# sch.net
KiCad netlist of a schematic drawn in Altium Designer
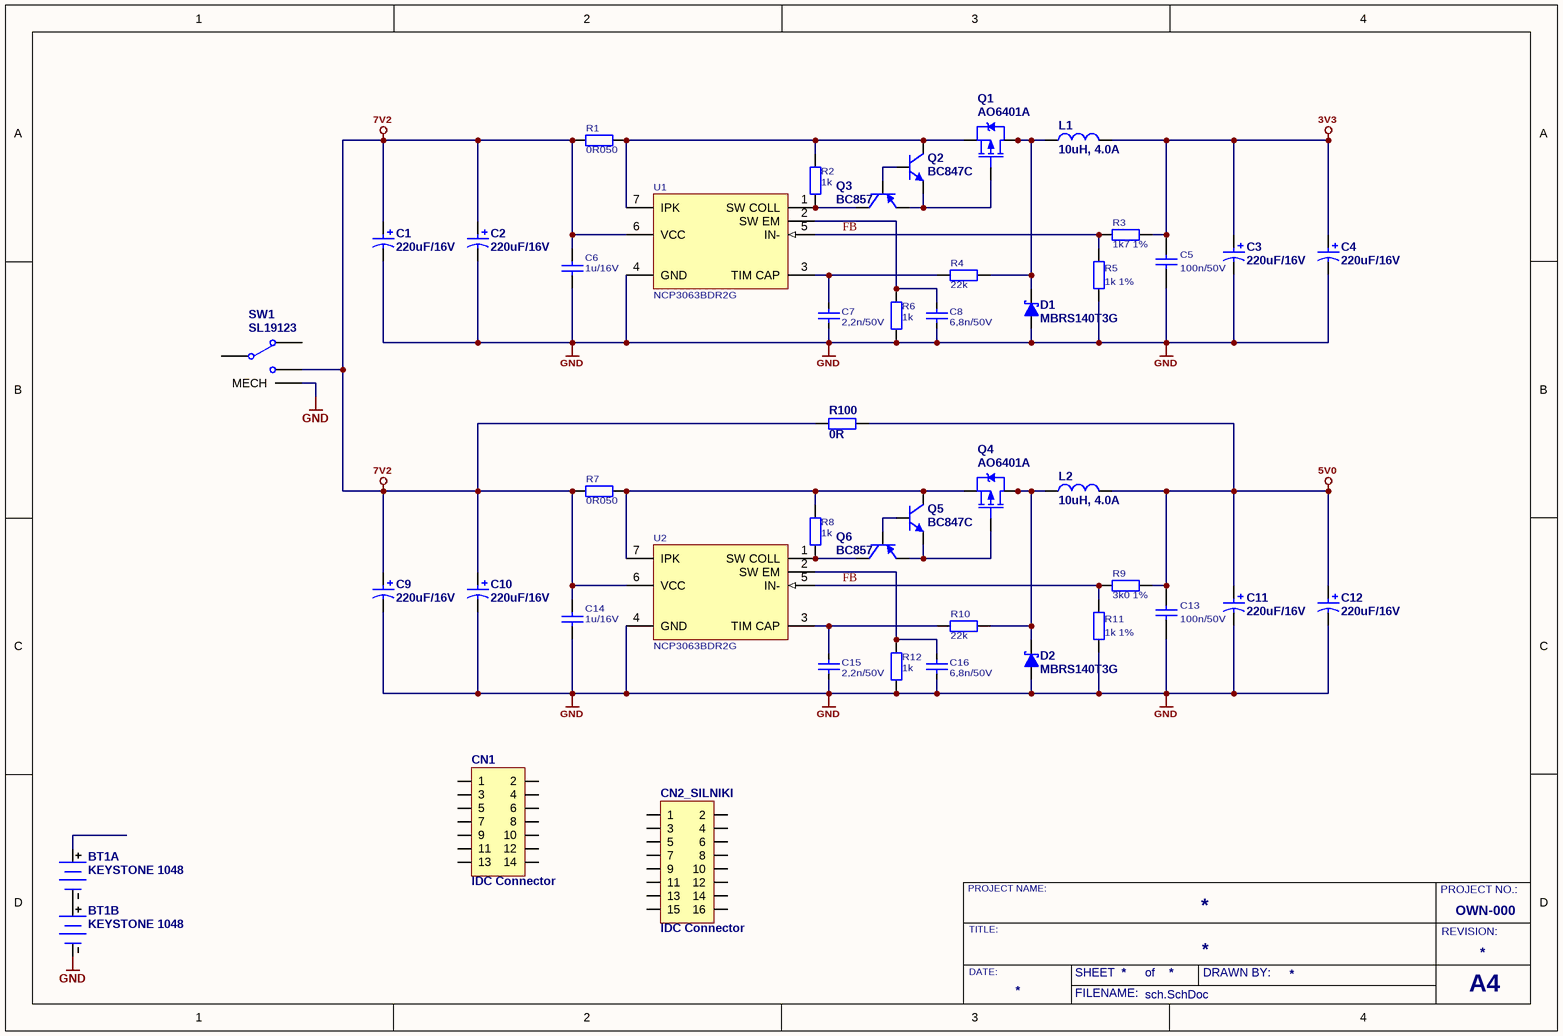
[diagram p0: sch.SchDoc]

(export (version "E")
  (design (tool "Eeschema 10.0.6"))
  (components
    (comp (ref "BT1")
      (value "KEYSTONE 1048")
      (footprint "KEYSTONE_1048")
      (description "2x 18650 LiPo Acu in the KEYSTONE 1048 Holder")
      (libsource (lib "baterries_and_accus") (part "18650_x2"))
    )
    (comp (ref "C1")
      (value "220uF/16V")
      (footprint "CES_E_8.3x8.3_6.2")
      (description "Polarized Capacitor")
      (libsource (lib "capacitors") (part "Cap Pol"))
    )
    (comp (ref "C2")
      (value "220uF/16V")
      (footprint "CES_E_8.3x8.3_6.2")
      (description "Polarized Capacitor")
      (libsource (lib "capacitors") (part "Cap Pol"))
    )
    (comp (ref "C3")
      (value "220uF/16V")
      (footprint "CES_E_8.3x8.3_6.2")
      (description "Polarized Capacitor")
      (libsource (lib "capacitors") (part "Cap Pol"))
    )
    (comp (ref "C4")
      (value "220uF/16V")
      (footprint "CES_E_8.3x8.3_6.2")
      (description "Polarized Capacitor")
      (libsource (lib "capacitors") (part "Cap Pol"))
    )
    (comp (ref "C5")
      (value "100n/50V")
      (footprint "C0805")
      (description "Capacitor")
      (libsource (lib "") (part "Cap_1"))
    )
    (comp (ref "C6")
      (value "1u/16V")
      (footprint "C0805")
      (description "Capacitor")
      (libsource (lib "") (part "Cap_2"))
    )
    (comp (ref "C7")
      (value "2,2n/50V")
      (footprint "C0805")
      (description "Capacitor")
      (libsource (lib "capacitors") (part "Cap"))
    )
    (comp (ref "C8")
      (value "6,8n/50V")
      (footprint "C0805")
      (description "Capacitor")
      (libsource (lib "capacitors") (part "Cap"))
    )
    (comp (ref "C9")
      (value "220uF/16V")
      (footprint "CES_E_8.3x8.3_6.2")
      (description "Polarized Capacitor")
      (libsource (lib "capacitors") (part "Cap Pol"))
    )
    (comp (ref "C10")
      (value "220uF/16V")
      (footprint "CES_E_8.3x8.3_6.2")
      (description "Polarized Capacitor")
      (libsource (lib "capacitors") (part "Cap Pol"))
    )
    (comp (ref "C11")
      (value "220uF/16V")
      (footprint "CES_E_8.3x8.3_6.2")
      (description "Polarized Capacitor")
      (libsource (lib "capacitors") (part "Cap Pol"))
    )
    (comp (ref "C12")
      (value "220uF/16V")
      (footprint "CES_E_8.3x8.3_6.2")
      (description "Polarized Capacitor")
      (libsource (lib "capacitors") (part "Cap Pol"))
    )
    (comp (ref "C13")
      (value "100n/50V")
      (footprint "C0805")
      (description "Capacitor")
      (libsource (lib "") (part "Cap_1"))
    )
    (comp (ref "C14")
      (value "1u/16V")
      (footprint "C0805")
      (description "Capacitor")
      (libsource (lib "") (part "Cap_2"))
    )
    (comp (ref "C15")
      (value "2,2n/50V")
      (footprint "C0805")
      (description "Capacitor")
      (libsource (lib "capacitors") (part "Cap"))
    )
    (comp (ref "C16")
      (value "6,8n/50V")
      (footprint "C0805")
      (description "Capacitor")
      (libsource (lib "capacitors") (part "Cap"))
    )
    (comp (ref "CN1") (value "IDC Connector") (footprint "IDC14_RA") (libsource (lib "idc") (part "CN_7x2")))
    (comp (ref "CN2_SILNIKI")
      (value "IDC Connector")
      (footprint "IDC16_RA")
      (libsource (lib "idc") (part "CN_8x2"))
    )
    (comp (ref "D1")
      (value "MBRS140T3G")
      (footprint "SMB")
      (description "Schottky barrier rectifier: 40V, 1A")
      (libsource (lib "diodes_schottky") (part "MBRS140T3G"))
    )
    (comp (ref "D2")
      (value "MBRS140T3G")
      (footprint "SMB")
      (description "Schottky barrier rectifier: 40V, 1A")
      (libsource (lib "diodes_schottky") (part "MBRS140T3G"))
    )
    (comp (ref "L1")
      (value "10uH, 4.0A")
      (footprint "DE1205")
      (description "DE1205-10")
      (libsource (lib "inductors") (part "DE1205-10"))
    )
    (comp (ref "L2")
      (value "10uH, 4.0A")
      (footprint "DE1205")
      (description "DE1205-10")
      (libsource (lib "inductors") (part "DE1205-10"))
    )
    (comp (ref "Q1")
      (value "AO6401A")
      (footprint "SOT-23-6")
      (description "P-Channel MOSFET; -60V, -5A, 1.3W;")
      (libsource (lib "transistors_mos") (part "AO6401A"))
    )
    (comp (ref "Q2")
      (value "BC847C")
      (footprint "SOT-23")
      (description "NPN General Purpose Transistor (VCE=45V, IC=100mA, HFE=420-800)")
      (libsource (lib "transistors_bjt") (part "BC847C"))
    )
    (comp (ref "Q3")
      (value "BC857")
      (footprint "SOT-23")
      (description "PNP General Purpose Transistor (VCE=-45V, IC=-100mA)")
      (libsource (lib "transistors_bjt") (part "BC857"))
    )
    (comp (ref "Q4")
      (value "AO6401A")
      (footprint "SOT-23-6")
      (description "P-Channel MOSFET; -60V, -5A, 1.3W;")
      (libsource (lib "transistors_mos") (part "AO6401A"))
    )
    (comp (ref "Q5")
      (value "BC847C")
      (footprint "SOT-23")
      (description "NPN General Purpose Transistor (VCE=45V, IC=100mA, HFE=420-800)")
      (libsource (lib "transistors_bjt") (part "BC847C"))
    )
    (comp (ref "Q6")
      (value "BC857")
      (footprint "SOT-23")
      (description "PNP General Purpose Transistor (VCE=-45V, IC=-100mA)")
      (libsource (lib "transistors_bjt") (part "BC857"))
    )
    (comp (ref "R1")
      (value "0R050")
      (footprint "R0805")
      (description "Resistor")
      (libsource (lib "") (part "Res_3"))
    )
    (comp (ref "R2")
      (value "1k")
      (footprint "R0805")
      (description "Resistor")
      (libsource (lib "") (part "Res_1"))
    )
    (comp (ref "R3")
      (value "1k7 1%")
      (footprint "R0805")
      (description "Resistor")
      (libsource (lib "") (part "Res_3"))
    )
    (comp (ref "R4")
      (value "22k")
      (footprint "R0805")
      (description "Resistor")
      (libsource (lib "resistors") (part "Res"))
    )
    (comp (ref "R5")
      (value "1k 1%")
      (footprint "R0805")
      (description "Resistor")
      (libsource (lib "") (part "Res_1"))
    )
    (comp (ref "R6")
      (value "1k")
      (footprint "R0805")
      (description "Resistor")
      (libsource (lib "") (part "Res_1"))
    )
    (comp (ref "R7")
      (value "0R050")
      (footprint "R0805")
      (description "Resistor")
      (libsource (lib "") (part "Res_3"))
    )
    (comp (ref "R8")
      (value "1k")
      (footprint "R0805")
      (description "Resistor")
      (libsource (lib "") (part "Res_1"))
    )
    (comp (ref "R9")
      (value "3k0 1%")
      (footprint "R0805")
      (description "Resistor")
      (libsource (lib "") (part "Res_3"))
    )
    (comp (ref "R10")
      (value "22k")
      (footprint "R0805")
      (description "Resistor")
      (libsource (lib "resistors") (part "Res"))
    )
    (comp (ref "R11")
      (value "1k 1%")
      (footprint "R0805")
      (description "Resistor")
      (libsource (lib "") (part "Res_1"))
    )
    (comp (ref "R12")
      (value "1k")
      (footprint "R0805")
      (description "Resistor")
      (libsource (lib "") (part "Res_1"))
    )
    (comp (ref "R100")
      (value "0R")
      (footprint "R1206")
      (description "Resistor")
      (libsource (lib "") (part "Res_2"))
    )
    (comp (ref "SW1")
      (value "SL19123")
      (footprint "500SSPxS1M6xEA")
      (description "Canal Electronic SPDT AC: 3A/250V, DC: 6A/28V")
      (libsource (lib "switches_slide") (part "SL19123"))
    )
    (comp (ref "U1")
      (value "NCP3063BDR2G")
      (footprint "SO8")
      (description "DC-DC Converter NCP3063BDR2G (Farnell 1547126)")
      (libsource (lib "switched_voltage_regulators") (part "NCP3063BDR2G"))
    )
    (comp (ref "U2")
      (value "NCP3063BDR2G")
      (footprint "SO8")
      (description "DC-DC Converter NCP3063BDR2G (Farnell 1547126)")
      (libsource (lib "switched_voltage_regulators") (part "NCP3063BDR2G"))
    )
  )
  (nets
    (net (code "1") (name "/FB") (class "Default")
      (node (ref "R11") (pin "1") (pinfunction "1_1") (pintype "passive"))
      (node (ref "R3") (pin "1") (pinfunction "1_1") (pintype "passive"))
      (node (ref "R5") (pin "1") (pinfunction "1_1") (pintype "passive"))
      (node (ref "R9") (pin "1") (pinfunction "1_1") (pintype "passive"))
      (node (ref "U1") (pin "5") (pinfunction "IN-_5") (pintype "input"))
      (node (ref "U2") (pin "5") (pinfunction "IN-_5") (pintype "input"))
    )
    (net (code "2") (name "3V3") (class "Default")
      (node (ref "C3") (pin "1") (pinfunction "1_1") (pintype "passive"))
      (node (ref "C4") (pin "1") (pinfunction "1_1") (pintype "passive"))
      (node (ref "C5") (pin "2") (pinfunction "2_2") (pintype "passive"))
      (node (ref "L1") (pin "2") (pinfunction "2_2") (pintype "passive"))
      (node (ref "R3") (pin "2") (pinfunction "2_2") (pintype "passive"))
    )
    (net (code "3") (name "5V0") (class "Default")
      (node (ref "C11") (pin "1") (pinfunction "1_1") (pintype "passive"))
      (node (ref "C12") (pin "1") (pinfunction "1_1") (pintype "passive"))
      (node (ref "C13") (pin "2") (pinfunction "2_2") (pintype "passive"))
      (node (ref "L2") (pin "2") (pinfunction "2_2") (pintype "passive"))
      (node (ref "R100") (pin "2") (pinfunction "2_2") (pintype "passive"))
      (node (ref "R9") (pin "2") (pinfunction "2_2") (pintype "passive"))
    )
    (net (code "4") (name "7V2") (class "Default")
      (node (ref "C1") (pin "1") (pinfunction "1_1") (pintype "passive"))
      (node (ref "C10") (pin "1") (pinfunction "1_1") (pintype "passive"))
      (node (ref "C14") (pin "2") (pinfunction "2_2") (pintype "passive"))
      (node (ref "C2") (pin "1") (pinfunction "1_1") (pintype "passive"))
      (node (ref "C6") (pin "2") (pinfunction "2_2") (pintype "passive"))
      (node (ref "C9") (pin "1") (pinfunction "1_1") (pintype "passive"))
      (node (ref "R1") (pin "1") (pinfunction "1_1") (pintype "passive"))
      (node (ref "R100") (pin "1") (pinfunction "1_1") (pintype "passive"))
      (node (ref "R7") (pin "1") (pinfunction "1_1") (pintype "passive"))
      (node (ref "SW1") (pin "3") (pinfunction "3_3") (pintype "passive"))
      (node (ref "U1") (pin "6") (pinfunction "VCC_6") (pintype "power_in"))
      (node (ref "U2") (pin "6") (pinfunction "VCC_6") (pintype "power_in"))
    )
    (net (code "5") (name "GND") (class "Default")
      (node (ref "BT1") (pin "3") (pinfunction "-_3") (pintype "passive"))
      (node (ref "C1") (pin "2") (pinfunction "2_2") (pintype "passive"))
      (node (ref "C10") (pin "2") (pinfunction "2_2") (pintype "passive"))
      (node (ref "C11") (pin "2") (pinfunction "2_2") (pintype "passive"))
      (node (ref "C12") (pin "2") (pinfunction "2_2") (pintype "passive"))
      (node (ref "C13") (pin "1") (pinfunction "1_1") (pintype "passive"))
      (node (ref "C14") (pin "1") (pinfunction "1_1") (pintype "passive"))
      (node (ref "C15") (pin "1") (pinfunction "1_1") (pintype "passive"))
      (node (ref "C16") (pin "1") (pinfunction "1_1") (pintype "passive"))
      (node (ref "C2") (pin "2") (pinfunction "2_2") (pintype "passive"))
      (node (ref "C3") (pin "2") (pinfunction "2_2") (pintype "passive"))
      (node (ref "C4") (pin "2") (pinfunction "2_2") (pintype "passive"))
      (node (ref "C5") (pin "1") (pinfunction "1_1") (pintype "passive"))
      (node (ref "C6") (pin "1") (pinfunction "1_1") (pintype "passive"))
      (node (ref "C7") (pin "1") (pinfunction "1_1") (pintype "passive"))
      (node (ref "C8") (pin "1") (pinfunction "1_1") (pintype "passive"))
      (node (ref "C9") (pin "2") (pinfunction "2_2") (pintype "passive"))
      (node (ref "D1") (pin "1") (pinfunction "A_1") (pintype "passive"))
      (node (ref "D2") (pin "1") (pinfunction "A_1") (pintype "passive"))
      (node (ref "R11") (pin "2") (pinfunction "2_2") (pintype "passive"))
      (node (ref "R12") (pin "2") (pinfunction "2_2") (pintype "passive"))
      (node (ref "R5") (pin "2") (pinfunction "2_2") (pintype "passive"))
      (node (ref "R6") (pin "2") (pinfunction "2_2") (pintype "passive"))
      (node (ref "SW1") (pin "M") (pinfunction "MECH_M") (pintype "passive"))
      (node (ref "U1") (pin "4") (pinfunction "GND_4") (pintype "power_in"))
      (node (ref "U2") (pin "4") (pinfunction "GND_4") (pintype "power_in"))
    )
    (net (code "6") (name "Net-(BT1A--)") (class "Default")
      (node (ref "BT1") (pin "2") (pinfunction "-_2") (pintype "passive"))
      (node (ref "BT1") (pin "4") (pinfunction "+_4") (pintype "passive"))
    )
    (net (code "7") (name "Net-(D1-K)") (class "Default")
      (node (ref "D1") (pin "2") (pinfunction "K_2") (pintype "passive"))
      (node (ref "L1") (pin "1") (pinfunction "1_1") (pintype "passive"))
      (node (ref "Q1") (pin "1") (pinfunction "D_1") (pintype "passive"))
      (node (ref "Q1") (pin "2") (pinfunction "D_2") (pintype "passive"))
      (node (ref "Q1") (pin "5") (pinfunction "D_5") (pintype "passive"))
      (node (ref "Q1") (pin "6") (pinfunction "D_6") (pintype "passive"))
      (node (ref "R4") (pin "1") (pinfunction "1_1") (pintype "passive"))
    )
    (net (code "8") (name "Net-(D2-K)") (class "Default")
      (node (ref "D2") (pin "2") (pinfunction "K_2") (pintype "passive"))
      (node (ref "L2") (pin "1") (pinfunction "1_1") (pintype "passive"))
      (node (ref "Q4") (pin "1") (pinfunction "D_1") (pintype "passive"))
      (node (ref "Q4") (pin "2") (pinfunction "D_2") (pintype "passive"))
      (node (ref "Q4") (pin "5") (pinfunction "D_5") (pintype "passive"))
      (node (ref "Q4") (pin "6") (pinfunction "D_6") (pintype "passive"))
      (node (ref "R10") (pin "1") (pinfunction "1_1") (pintype "passive"))
    )
    (net (code "9") (name "Net-(Q1-G)") (class "Default")
      (node (ref "Q1") (pin "3") (pinfunction "G_3") (pintype "passive"))
      (node (ref "Q2") (pin "2") (pinfunction "E_2") (pintype "passive"))
      (node (ref "Q3") (pin "2") (pinfunction "E_2") (pintype "passive"))
    )
    (net (code "10") (name "Net-(Q1-S)") (class "Default")
      (node (ref "Q1") (pin "4") (pinfunction "S_4") (pintype "passive"))
      (node (ref "Q2") (pin "3") (pinfunction "C_3") (pintype "passive"))
      (node (ref "R1") (pin "2") (pinfunction "2_2") (pintype "passive"))
      (node (ref "R2") (pin "1") (pinfunction "1_1") (pintype "passive"))
      (node (ref "U1") (pin "7") (pinfunction "IPK_7") (pintype "passive"))
    )
    (net (code "11") (name "Net-(Q2-B)") (class "Default")
      (node (ref "Q2") (pin "1") (pinfunction "B_1") (pintype "passive"))
      (node (ref "Q3") (pin "1") (pinfunction "B_1") (pintype "passive"))
    )
    (net (code "12") (name "Net-(Q3-C)") (class "Default")
      (node (ref "Q3") (pin "3") (pinfunction "C_3") (pintype "passive"))
      (node (ref "R2") (pin "2") (pinfunction "2_2") (pintype "passive"))
      (node (ref "U1") (pin "1") (pinfunction "SW_COLL_1") (pintype "passive"))
    )
    (net (code "13") (name "Net-(Q4-G)") (class "Default")
      (node (ref "Q4") (pin "3") (pinfunction "G_3") (pintype "passive"))
      (node (ref "Q5") (pin "2") (pinfunction "E_2") (pintype "passive"))
      (node (ref "Q6") (pin "2") (pinfunction "E_2") (pintype "passive"))
    )
    (net (code "14") (name "Net-(Q4-S)") (class "Default")
      (node (ref "Q4") (pin "4") (pinfunction "S_4") (pintype "passive"))
      (node (ref "Q5") (pin "3") (pinfunction "C_3") (pintype "passive"))
      (node (ref "R7") (pin "2") (pinfunction "2_2") (pintype "passive"))
      (node (ref "R8") (pin "1") (pinfunction "1_1") (pintype "passive"))
      (node (ref "U2") (pin "7") (pinfunction "IPK_7") (pintype "passive"))
    )
    (net (code "15") (name "Net-(Q5-B)") (class "Default")
      (node (ref "Q5") (pin "1") (pinfunction "B_1") (pintype "passive"))
      (node (ref "Q6") (pin "1") (pinfunction "B_1") (pintype "passive"))
    )
    (net (code "16") (name "Net-(Q6-C)") (class "Default")
      (node (ref "Q6") (pin "3") (pinfunction "C_3") (pintype "passive"))
      (node (ref "R8") (pin "2") (pinfunction "2_2") (pintype "passive"))
      (node (ref "U2") (pin "1") (pinfunction "SW_COLL_1") (pintype "passive"))
    )
    (net (code "17") (name "Net-(U1-SW_EM)") (class "Default")
      (node (ref "C8") (pin "2") (pinfunction "2_2") (pintype "passive"))
      (node (ref "R6") (pin "1") (pinfunction "1_1") (pintype "passive"))
      (node (ref "U1") (pin "2") (pinfunction "SW_EM_2") (pintype "passive"))
    )
    (net (code "18") (name "Net-(U1-TIM_CAP)") (class "Default")
      (node (ref "C7") (pin "2") (pinfunction "2_2") (pintype "passive"))
      (node (ref "R4") (pin "2") (pinfunction "2_2") (pintype "passive"))
      (node (ref "U1") (pin "3") (pinfunction "TIM_CAP_3") (pintype "passive"))
    )
    (net (code "19") (name "Net-(U2-SW_EM)") (class "Default")
      (node (ref "C16") (pin "2") (pinfunction "2_2") (pintype "passive"))
      (node (ref "R12") (pin "1") (pinfunction "1_1") (pintype "passive"))
      (node (ref "U2") (pin "2") (pinfunction "SW_EM_2") (pintype "passive"))
    )
    (net (code "20") (name "Net-(U2-TIM_CAP)") (class "Default")
      (node (ref "C15") (pin "2") (pinfunction "2_2") (pintype "passive"))
      (node (ref "R10") (pin "2") (pinfunction "2_2") (pintype "passive"))
      (node (ref "U2") (pin "3") (pinfunction "TIM_CAP_3") (pintype "passive"))
    )
    (net (code "21") (name "unconnected-(BT1A-+-Pad1)") (class "Default")
      (node (ref "BT1") (pin "1") (pinfunction "+_1") (pintype "passive"))
    )
    (net (code "22") (name "unconnected-(CN1-Pad1)") (class "Default")
      (node (ref "CN1") (pin "1") (pinfunction "1_1") (pintype "passive"))
    )
    (net (code "23") (name "unconnected-(CN1-Pad2)") (class "Default")
      (node (ref "CN1") (pin "2") (pinfunction "2_2") (pintype "passive"))
    )
    (net (code "24") (name "unconnected-(CN1-Pad3)") (class "Default")
      (node (ref "CN1") (pin "3") (pinfunction "3_3") (pintype "passive"))
    )
    (net (code "25") (name "unconnected-(CN1-Pad4)") (class "Default")
      (node (ref "CN1") (pin "4") (pinfunction "4_4") (pintype "passive"))
    )
    (net (code "26") (name "unconnected-(CN1-Pad5)") (class "Default")
      (node (ref "CN1") (pin "5") (pinfunction "5_5") (pintype "passive"))
    )
    (net (code "27") (name "unconnected-(CN1-Pad6)") (class "Default")
      (node (ref "CN1") (pin "6") (pinfunction "6_6") (pintype "passive"))
    )
    (net (code "28") (name "unconnected-(CN1-Pad7)") (class "Default")
      (node (ref "CN1") (pin "7") (pinfunction "7_7") (pintype "passive"))
    )
    (net (code "29") (name "unconnected-(CN1-Pad8)") (class "Default")
      (node (ref "CN1") (pin "8") (pinfunction "8_8") (pintype "passive"))
    )
    (net (code "30") (name "unconnected-(CN1-Pad9)") (class "Default")
      (node (ref "CN1") (pin "9") (pinfunction "9_9") (pintype "passive"))
    )
    (net (code "31") (name "unconnected-(CN1-Pad10)") (class "Default")
      (node (ref "CN1") (pin "10") (pinfunction "10_10") (pintype "passive"))
    )
    (net (code "32") (name "unconnected-(CN1-Pad11)") (class "Default")
      (node (ref "CN1") (pin "11") (pinfunction "11_11") (pintype "passive"))
    )
    (net (code "33") (name "unconnected-(CN1-Pad12)") (class "Default")
      (node (ref "CN1") (pin "12") (pinfunction "12_12") (pintype "passive"))
    )
    (net (code "34") (name "unconnected-(CN1-Pad13)") (class "Default")
      (node (ref "CN1") (pin "13") (pinfunction "13_13") (pintype "passive"))
    )
    (net (code "35") (name "unconnected-(CN1-Pad14)") (class "Default")
      (node (ref "CN1") (pin "14") (pinfunction "14_14") (pintype "passive"))
    )
    (net (code "36") (name "unconnected-(CN2_SILNIKI-Pad1)") (class "Default")
      (node (ref "CN2_SILNIKI") (pin "1") (pinfunction "1_1") (pintype "passive"))
    )
    (net (code "37") (name "unconnected-(CN2_SILNIKI-Pad2)") (class "Default")
      (node (ref "CN2_SILNIKI") (pin "2") (pinfunction "2_2") (pintype "passive"))
    )
    (net (code "38") (name "unconnected-(CN2_SILNIKI-Pad3)") (class "Default")
      (node (ref "CN2_SILNIKI") (pin "3") (pinfunction "3_3") (pintype "passive"))
    )
    (net (code "39") (name "unconnected-(CN2_SILNIKI-Pad4)") (class "Default")
      (node (ref "CN2_SILNIKI") (pin "4") (pinfunction "4_4") (pintype "passive"))
    )
    (net (code "40") (name "unconnected-(CN2_SILNIKI-Pad5)") (class "Default")
      (node (ref "CN2_SILNIKI") (pin "5") (pinfunction "5_5") (pintype "passive"))
    )
    (net (code "41") (name "unconnected-(CN2_SILNIKI-Pad6)") (class "Default")
      (node (ref "CN2_SILNIKI") (pin "6") (pinfunction "6_6") (pintype "passive"))
    )
    (net (code "42") (name "unconnected-(CN2_SILNIKI-Pad7)") (class "Default")
      (node (ref "CN2_SILNIKI") (pin "7") (pinfunction "7_7") (pintype "passive"))
    )
    (net (code "43") (name "unconnected-(CN2_SILNIKI-Pad8)") (class "Default")
      (node (ref "CN2_SILNIKI") (pin "8") (pinfunction "8_8") (pintype "passive"))
    )
    (net (code "44") (name "unconnected-(CN2_SILNIKI-Pad9)") (class "Default")
      (node (ref "CN2_SILNIKI") (pin "9") (pinfunction "9_9") (pintype "passive"))
    )
    (net (code "45") (name "unconnected-(CN2_SILNIKI-Pad10)") (class "Default")
      (node (ref "CN2_SILNIKI") (pin "10") (pinfunction "10_10") (pintype "passive"))
    )
    (net (code "46") (name "unconnected-(CN2_SILNIKI-Pad11)") (class "Default")
      (node (ref "CN2_SILNIKI") (pin "11") (pinfunction "11_11") (pintype "passive"))
    )
    (net (code "47") (name "unconnected-(CN2_SILNIKI-Pad12)") (class "Default")
      (node (ref "CN2_SILNIKI") (pin "12") (pinfunction "12_12") (pintype "passive"))
    )
    (net (code "48") (name "unconnected-(CN2_SILNIKI-Pad13)") (class "Default")
      (node (ref "CN2_SILNIKI") (pin "13") (pinfunction "13_13") (pintype "passive"))
    )
    (net (code "49") (name "unconnected-(CN2_SILNIKI-Pad14)") (class "Default")
      (node (ref "CN2_SILNIKI") (pin "14") (pinfunction "14_14") (pintype "passive"))
    )
    (net (code "50") (name "unconnected-(CN2_SILNIKI-Pad15)") (class "Default")
      (node (ref "CN2_SILNIKI") (pin "15") (pinfunction "15_15") (pintype "passive"))
    )
    (net (code "51") (name "unconnected-(CN2_SILNIKI-Pad16)") (class "Default")
      (node (ref "CN2_SILNIKI") (pin "16") (pinfunction "16_16") (pintype "passive"))
    )
    (net (code "52") (name "unconnected-(SW1-Pad1)") (class "Default")
      (node (ref "SW1") (pin "1") (pinfunction "1_1") (pintype "passive"))
    )
    (net (code "53") (name "unconnected-(SW1-Pad2)") (class "Default")
      (node (ref "SW1") (pin "2") (pinfunction "2_2") (pintype "passive"))
    )
  )
)
